# Analog_Inputs.net
KiCad netlist of a schematic drawn in Altium Designer
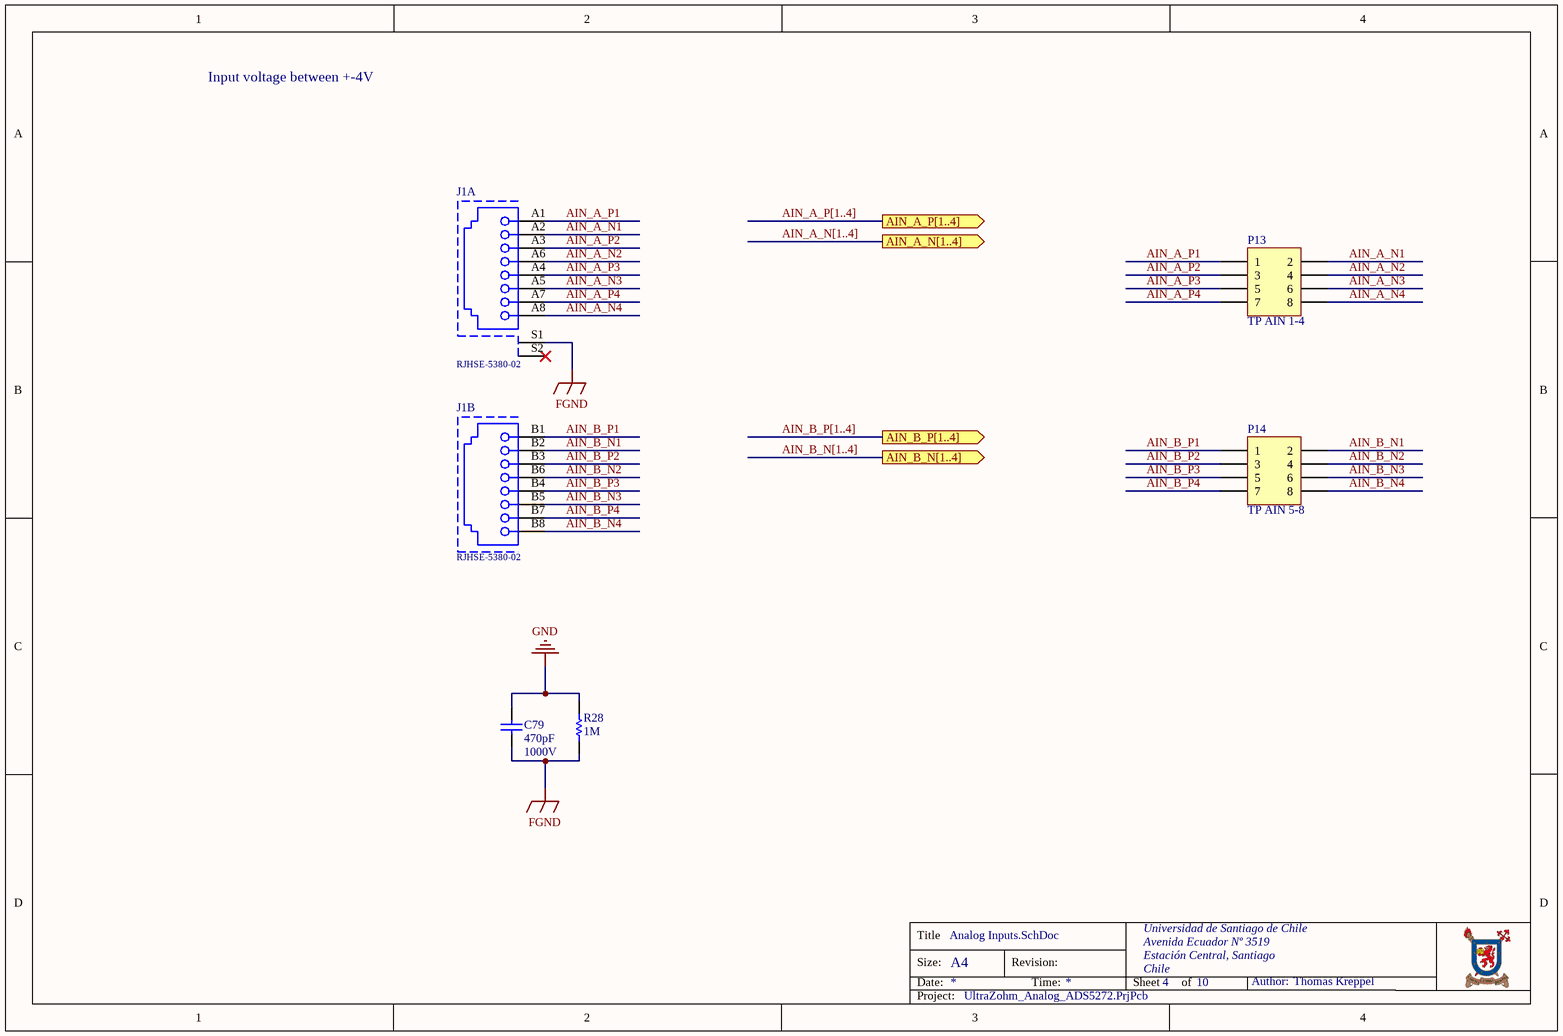
[diagram p0: Analog Inputs.SchDoc]

(export (version "E")
  (design (tool "Eeschema 10.0.6"))
  (components
    (comp (ref "C79")
      (value "470pF")
      (footprint "RES_1206")
      (description "Capacitor")
      (fields
        (field (name "MPN") "885342208017")
        (field (name "VOLTAGE") "1000V")
        (field (name "MF") "Würth Elektronik")
      )
      (libsource (lib "Componentes_SOC") (part "Cap_1206"))
    )
    (comp (ref "J1")
      (value "RJHSE-5380-02")
      (footprint "RJHSE-5380-02")
      (description "Modular Jack WR-MJ, Tab Up, Shielded, Dual Port, Righ Angle, THT, 8P8C")
      (fields (field (name "MANUFACTURER") "Amphenol"))
      (libsource (lib "Componentes_SOC") (part "RJHSE-5380-02"))
    )
    (comp (ref "P13")
      (value "TP AIN 1-4")
      (footprint "HDR2X4")
      (description "Header, 4-Pin, Dual row")
      (fields (field (name "PUBLISHER") "Altium Limited"))
      (libsource (lib "Miscellaneous Connectors") (part "Header 4X2"))
    )
    (comp (ref "P14")
      (value "TP AIN 5-8")
      (footprint "HDR2X4")
      (description "Header, 4-Pin, Dual row")
      (fields (field (name "PUBLISHER") "Altium Limited"))
      (libsource (lib "Miscellaneous Connectors") (part "Header 4X2"))
    )
    (comp (ref "R28")
      (value "1M")
      (footprint "RES_1206")
      (description "Resistor")
      (fields (field (name "TOLERANCE") "1%"))
      (libsource (lib "Componentes_SOC") (part "Res1206"))
    )
  )
  (nets
    (net (code "1") (name "/AIN_A_N1") (class "Default")
      (node (ref "J1") (pin "A2") (pinfunction "A2_A2") (pintype "passive"))
      (node (ref "P13") (pin "2") (pinfunction "2_2") (pintype "passive"))
    )
    (net (code "2") (name "/AIN_A_N2") (class "Default")
      (node (ref "J1") (pin "A6") (pinfunction "A6_A6") (pintype "passive"))
      (node (ref "P13") (pin "4") (pinfunction "4_4") (pintype "passive"))
    )
    (net (code "3") (name "/AIN_A_N3") (class "Default")
      (node (ref "J1") (pin "A5") (pinfunction "A5_A5") (pintype "passive"))
      (node (ref "P13") (pin "6") (pinfunction "6_6") (pintype "passive"))
    )
    (net (code "4") (name "/AIN_A_N4") (class "Default")
      (node (ref "J1") (pin "A8") (pinfunction "A8_A8") (pintype "passive"))
      (node (ref "P13") (pin "8") (pinfunction "8_8") (pintype "passive"))
    )
    (net (code "6") (name "/AIN_A_P1") (class "Default")
      (node (ref "J1") (pin "A1") (pinfunction "A1_A1") (pintype "passive"))
      (node (ref "P13") (pin "1") (pinfunction "1_1") (pintype "passive"))
    )
    (net (code "7") (name "/AIN_A_P2") (class "Default")
      (node (ref "J1") (pin "A3") (pinfunction "A3_A3") (pintype "passive"))
      (node (ref "P13") (pin "3") (pinfunction "3_3") (pintype "passive"))
    )
    (net (code "8") (name "/AIN_A_P3") (class "Default")
      (node (ref "J1") (pin "A4") (pinfunction "A4_A4") (pintype "passive"))
      (node (ref "P13") (pin "5") (pinfunction "5_5") (pintype "passive"))
    )
    (net (code "9") (name "/AIN_A_P4") (class "Default")
      (node (ref "J1") (pin "A7") (pinfunction "A7_A7") (pintype "passive"))
      (node (ref "P13") (pin "7") (pinfunction "7_7") (pintype "passive"))
    )
    (net (code "11") (name "/AIN_B_N1") (class "Default")
      (node (ref "J1") (pin "B2") (pinfunction "B2_B2") (pintype "passive"))
      (node (ref "P14") (pin "2") (pinfunction "2_2") (pintype "passive"))
    )
    (net (code "12") (name "/AIN_B_N2") (class "Default")
      (node (ref "J1") (pin "B6") (pinfunction "B6_B6") (pintype "passive"))
      (node (ref "P14") (pin "4") (pinfunction "4_4") (pintype "passive"))
    )
    (net (code "13") (name "/AIN_B_N3") (class "Default")
      (node (ref "J1") (pin "B5") (pinfunction "B5_B5") (pintype "passive"))
      (node (ref "P14") (pin "6") (pinfunction "6_6") (pintype "passive"))
    )
    (net (code "14") (name "/AIN_B_N4") (class "Default")
      (node (ref "J1") (pin "B8") (pinfunction "B8_B8") (pintype "passive"))
      (node (ref "P14") (pin "8") (pinfunction "8_8") (pintype "passive"))
    )
    (net (code "16") (name "/AIN_B_P1") (class "Default")
      (node (ref "J1") (pin "B1") (pinfunction "B1_B1") (pintype "passive"))
      (node (ref "P14") (pin "1") (pinfunction "1_1") (pintype "passive"))
    )
    (net (code "17") (name "/AIN_B_P2") (class "Default")
      (node (ref "J1") (pin "B3") (pinfunction "B3_B3") (pintype "passive"))
      (node (ref "P14") (pin "3") (pinfunction "3_3") (pintype "passive"))
    )
    (net (code "18") (name "/AIN_B_P3") (class "Default")
      (node (ref "J1") (pin "B4") (pinfunction "B4_B4") (pintype "passive"))
      (node (ref "P14") (pin "5") (pinfunction "5_5") (pintype "passive"))
    )
    (net (code "19") (name "/AIN_B_P4") (class "Default")
      (node (ref "J1") (pin "B7") (pinfunction "B7_B7") (pintype "passive"))
      (node (ref "P14") (pin "7") (pinfunction "7_7") (pintype "passive"))
    )
    (net (code "21") (name "FGND") (class "Default")
      (node (ref "C79") (pin "2") (pinfunction "2_2") (pintype "passive"))
      (node (ref "J1") (pin "S1") (pinfunction "S1_S1") (pintype "passive"))
      (node (ref "R28") (pin "1") (pinfunction "1_1") (pintype "passive"))
    )
    (net (code "22") (name "GND") (class "Default")
      (node (ref "C79") (pin "1") (pinfunction "1_1") (pintype "passive"))
      (node (ref "R28") (pin "2") (pinfunction "2_2") (pintype "passive"))
    )
    (net (code "23") (name "unconnected-(J1-PadS2)") (class "Default")
      (node (ref "J1") (pin "S2") (pinfunction "S2_S2") (pintype "passive+no_connect"))
    )
  )
)
